# Controller.net
KiCad netlist of a schematic drawn in Altium Designer
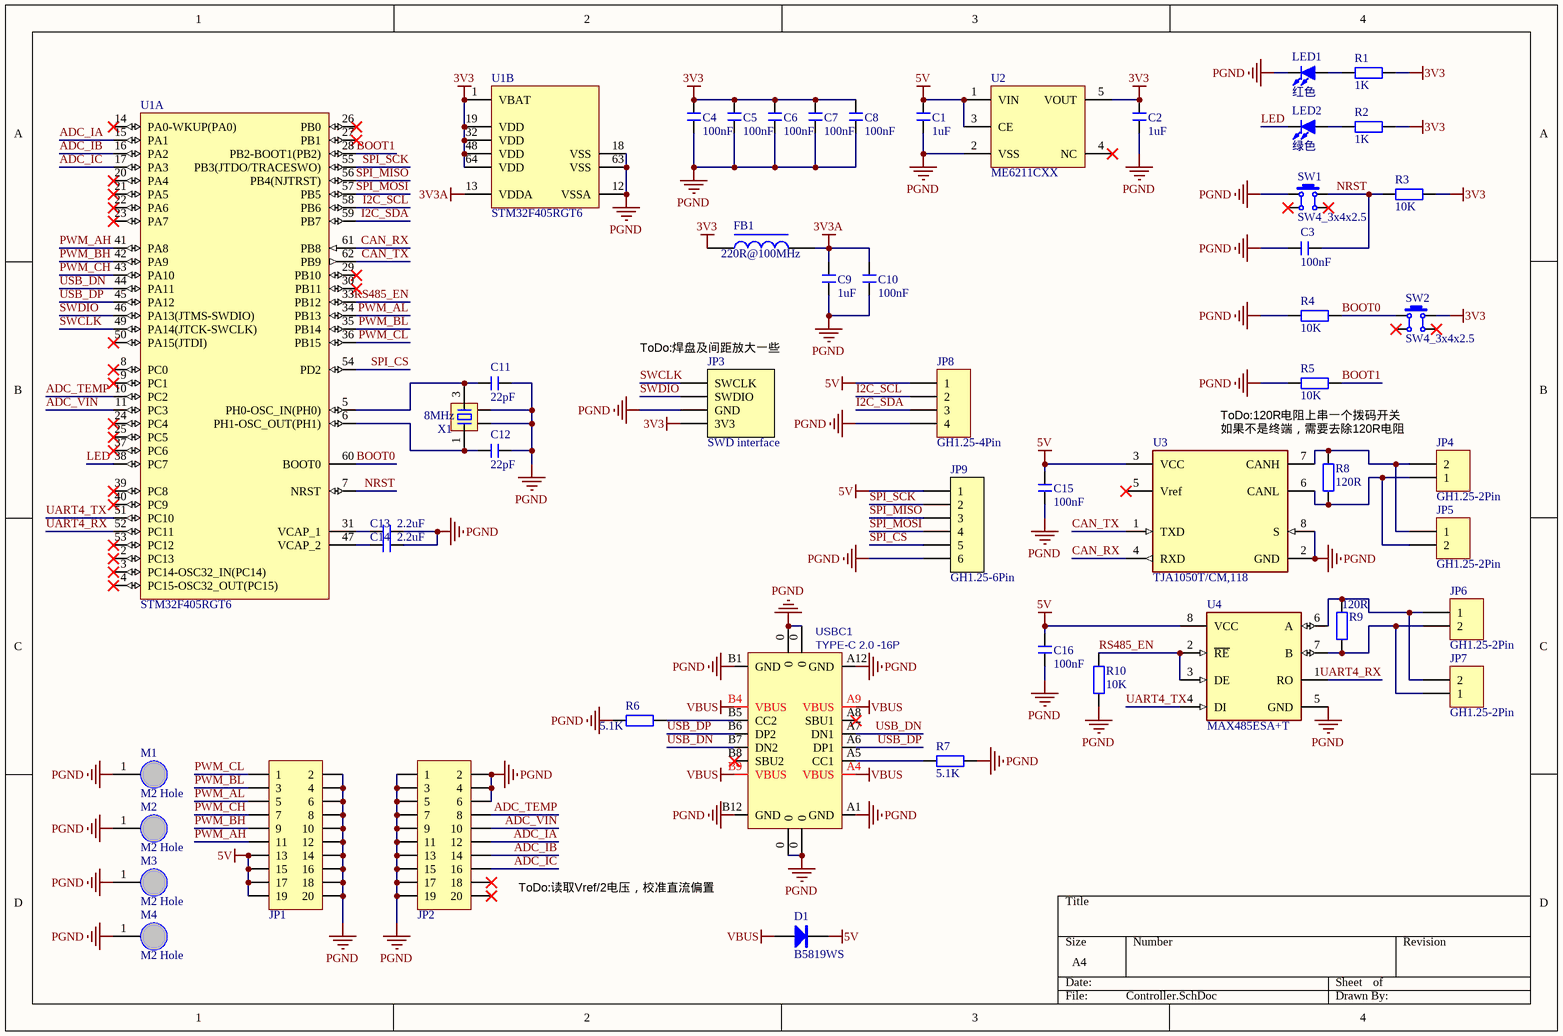
[diagram p0: Controller.SchDoc]

(export (version "E")
  (design (tool "Eeschema 10.0.6"))
  (components
    (comp (ref "C1")
      (value "1uF")
      (footprint "Capacitor_0402_SMD")
      (description "无极性贴片电容")
      (fields (field (name "版权归属") "源创客"))
      (libsource (lib "源创客") (part "C"))
    )
    (comp (ref "C2")
      (value "1uF")
      (footprint "Capacitor_0402_SMD")
      (description "无极性贴片电容")
      (fields (field (name "版权归属") "源创客"))
      (libsource (lib "源创客") (part "C"))
    )
    (comp (ref "C3")
      (value "100nF")
      (footprint "Capacitor_0402_SMD")
      (description "无极性贴片电容")
      (fields (field (name "版权归属") "源创客"))
      (libsource (lib "源创客") (part "C"))
    )
    (comp (ref "C4")
      (value "100nF")
      (footprint "Capacitor_0402_SMD")
      (description "无极性贴片电容")
      (fields (field (name "版权归属") "源创客"))
      (libsource (lib "源创客") (part "C"))
    )
    (comp (ref "C5")
      (value "100nF")
      (footprint "Capacitor_0402_SMD")
      (description "无极性贴片电容")
      (fields (field (name "版权归属") "源创客"))
      (libsource (lib "源创客") (part "C"))
    )
    (comp (ref "C6")
      (value "100nF")
      (footprint "Capacitor_0402_SMD")
      (description "无极性贴片电容")
      (fields (field (name "版权归属") "源创客"))
      (libsource (lib "源创客") (part "C"))
    )
    (comp (ref "C7")
      (value "100nF")
      (footprint "Capacitor_0402_SMD")
      (description "无极性贴片电容")
      (fields (field (name "版权归属") "源创客"))
      (libsource (lib "源创客") (part "C"))
    )
    (comp (ref "C8")
      (value "100nF")
      (footprint "Capacitor_0402_SMD")
      (description "无极性贴片电容")
      (fields (field (name "版权归属") "源创客"))
      (libsource (lib "源创客") (part "C"))
    )
    (comp (ref "C9")
      (value "1uF")
      (footprint "Capacitor_0402_SMD")
      (description "无极性贴片电容")
      (fields (field (name "版权归属") "源创客"))
      (libsource (lib "源创客") (part "C"))
    )
    (comp (ref "C10")
      (value "100nF")
      (footprint "Capacitor_0402_SMD")
      (description "无极性贴片电容")
      (fields (field (name "版权归属") "源创客"))
      (libsource (lib "源创客") (part "C"))
    )
    (comp (ref "C11")
      (value "22pF")
      (footprint "Capacitor_0402_SMD")
      (description "无极性贴片电容")
      (fields (field (name "版权归属") "源创客"))
      (libsource (lib "源创客") (part "C"))
    )
    (comp (ref "C12")
      (value "22pF")
      (footprint "Capacitor_0402_SMD")
      (description "无极性贴片电容")
      (fields (field (name "版权归属") "源创客"))
      (libsource (lib "源创客") (part "C"))
    )
    (comp (ref "C13")
      (value "2.2uF")
      (footprint "Capacitor_0402_SMD")
      (description "无极性贴片电容")
      (fields (field (name "版权归属") "源创客"))
      (libsource (lib "源创客") (part "C"))
    )
    (comp (ref "C14")
      (value "2.2uF")
      (footprint "Capacitor_0402_SMD")
      (description "无极性贴片电容")
      (fields (field (name "版权归属") "源创客"))
      (libsource (lib "源创客") (part "C"))
    )
    (comp (ref "C15")
      (value "100nF")
      (footprint "Capacitor_0402_SMD")
      (description "无极性贴片电容")
      (fields (field (name "版权归属") "源创客"))
      (libsource (lib "源创客") (part "C"))
    )
    (comp (ref "C16")
      (value "100nF")
      (footprint "Capacitor_0402_SMD")
      (description "无极性贴片电容")
      (fields (field (name "版权归属") "源创客"))
      (libsource (lib "源创客") (part "C"))
    )
    (comp (ref "D1")
      (value "B5819WS")
      (footprint "SOD323")
      (description "肖特基二极管")
      (fields (field (name "版权归属") "源创客"))
      (libsource (lib "源创客") (part "1N5819"))
    )
    (comp (ref "FB1")
      (value "220R@100MHz")
      (footprint "FerriteBead_0603_SMD")
      (description "FerriteBead")
      (libsource (lib "源创客") (part "FerriteBead"))
    )
    (comp (ref "JP1")
      (value "Header 2X10")
      (footprint "HDR2.0-LI-2x10P")
      (description "10*2P接插件")
      (libsource (lib "5.5 - 2.54mm(100mil)连接器(XH2.54)") (part "Header 10X2"))
    )
    (comp (ref "JP2")
      (value "Header 2X10")
      (footprint "HDR2.0-LI-2x10P")
      (description "10*2P接插件")
      (libsource (lib "5.5 - 2.54mm(100mil)连接器(XH2.54)") (part "Header 10X2"))
    )
    (comp (ref "JP3")
      (value "SWD interface")
      (footprint "SWD_interface")
      (libsource (lib "Controller") (part "SWD_interface"))
    )
    (comp (ref "JP4")
      (value "GH1.25-2Pin")
      (footprint "A1257WR-S-XP-2Pin")
      (description "CJTconn A1257 Series 1.25mm pitch wire to board connector")
      (libsource (lib "") (part "GH1.25-2Pin_1"))
    )
    (comp (ref "JP5")
      (value "GH1.25-2Pin")
      (footprint "A1257WR-S-XP-2Pin")
      (description "CJTconn A1257 Series 1.25mm pitch wire to board connector")
      (libsource (lib "接插件") (part "GH1.25-2Pin"))
    )
    (comp (ref "JP6")
      (value "GH1.25-2Pin")
      (footprint "A1257WR-S-XP-2Pin")
      (description "CJTconn A1257 Series 1.25mm pitch wire to board connector")
      (libsource (lib "接插件") (part "GH1.25-2Pin"))
    )
    (comp (ref "JP7")
      (value "GH1.25-2Pin")
      (footprint "A1257WR-S-XP-2Pin")
      (description "CJTconn A1257 Series 1.25mm pitch wire to board connector")
      (libsource (lib "") (part "GH1.25-2Pin_1"))
    )
    (comp (ref "JP8")
      (value "GH1.25-4Pin")
      (footprint "A1257WR-S-XP-4Pin")
      (description "CJTconn A1257 Series 1.25mm pitch wire to board connector")
      (libsource (lib "接插件") (part "GH1.25-4Pin"))
    )
    (comp (ref "JP9")
      (value "GH1.25-6Pin")
      (footprint "A1257WR-S-XP-6Pin")
      (description "CJTconn A1257 Series 1.25mm pitch wire to board connector")
      (libsource (lib "接插件") (part "GH1.25-6Pin"))
    )
    (comp (ref "LED1")
      (value "红色")
      (footprint "LED_0603_SMD_RED")
      (description "贴片LED")
      (fields (field (name "版权归属") "源创客"))
      (libsource (lib "源创客") (part "LED-SMD"))
    )
    (comp (ref "LED2")
      (value "绿色")
      (footprint "LED_0603_SMD_GREEN")
      (description "贴片LED")
      (fields (field (name "版权归属") "源创客"))
      (libsource (lib "源创客") (part "LED-SMD"))
    )
    (comp (ref "M1") (value "M2 Hole") (footprint "M2 Hole") (libsource (lib "Controller") (part "M2_hole")))
    (comp (ref "M2") (value "M2 Hole") (footprint "M2 Hole") (libsource (lib "Controller") (part "M2_hole")))
    (comp (ref "M3") (value "M2 Hole") (footprint "M2 Hole") (libsource (lib "Controller") (part "M2_hole")))
    (comp (ref "M4") (value "M2 Hole") (footprint "M2 Hole") (libsource (lib "Controller") (part "M2_hole")))
    (comp (ref "R1")
      (value "1K")
      (footprint "Resistor_0402_SMD")
      (description "贴片电阻")
      (fields (field (name "版权归属") "源创客"))
      (libsource (lib "源创客") (part "R"))
    )
    (comp (ref "R2")
      (value "1K")
      (footprint "Resistor_0402_SMD")
      (description "贴片电阻")
      (fields (field (name "版权归属") "源创客"))
      (libsource (lib "源创客") (part "R"))
    )
    (comp (ref "R3")
      (value "10K")
      (footprint "Resistor_0402_SMD")
      (description "贴片电阻")
      (fields (field (name "版权归属") "源创客"))
      (libsource (lib "源创客") (part "R"))
    )
    (comp (ref "R4")
      (value "10K")
      (footprint "Resistor_0402_SMD")
      (description "贴片电阻")
      (fields (field (name "版权归属") "源创客"))
      (libsource (lib "源创客") (part "R"))
    )
    (comp (ref "R5")
      (value "10K")
      (footprint "Resistor_0402_SMD")
      (description "贴片电阻")
      (fields (field (name "版权归属") "源创客"))
      (libsource (lib "源创客") (part "R"))
    )
    (comp (ref "R6")
      (value "5.1K")
      (footprint "Resistor_0402_SMD")
      (description "贴片电阻")
      (fields (field (name "版权归属") "源创客"))
      (libsource (lib "源创客") (part "R"))
    )
    (comp (ref "R7")
      (value "5.1K")
      (footprint "Resistor_0402_SMD")
      (description "贴片电阻")
      (fields (field (name "版权归属") "源创客"))
      (libsource (lib "源创客") (part "R"))
    )
    (comp (ref "R8")
      (value "120R")
      (footprint "Resistor_0402_SMD")
      (description "贴片电阻")
      (fields (field (name "版权归属") "源创客"))
      (libsource (lib "源创客") (part "R"))
    )
    (comp (ref "R9")
      (value "120R")
      (footprint "Resistor_0402_SMD")
      (description "贴片电阻")
      (fields (field (name "版权归属") "源创客"))
      (libsource (lib "源创客") (part "R"))
    )
    (comp (ref "R10")
      (value "10K")
      (footprint "Resistor_0402_SMD")
      (description "贴片电阻")
      (fields (field (name "版权归属") "源创客"))
      (libsource (lib "源创客") (part "R"))
    )
    (comp (ref "SW1")
      (value "SW4_3x4x2.5")
      (footprint "SW4_3x4x2.5")
      (libsource (lib "Controller") (part "SW4_3x4x2.5"))
    )
    (comp (ref "SW2")
      (value "SW4_3x4x2.5")
      (footprint "SW4_3x4x2.5")
      (libsource (lib "Controller") (part "SW4_3x4x2.5"))
    )
    (comp (ref "U1")
      (value "STM32F405RGT6")
      (footprint "STM-LQFP64_L")
      (fields (field (name "MANUFACTURER") "STMicroelectronics"))
      (libsource (lib "Altium Content Vault") (part "MC-ARM-STM32F4X5-SQ64"))
    )
    (comp (ref "U2")
      (value "ME6211CXX")
      (footprint "ME6211CXX")
      (description "高精度、高纹波抑制比、低噪声、超快响应 LDO")
      (libsource (lib "Controller") (part "ME6211CXX"))
    )
    (comp (ref "U3")
      (value "TJA1050T/CM,118")
      (footprint "FP-SOT96-1-IPC_C")
      (description "IC TRANSCEIVER HALF 1/1 8SO")
      (libsource (lib "Altium Content Vault") (part "cfdefafd38a55dc0607790f57b8a78f"))
    )
    (comp (ref "U4")
      (value "MAX485ESA+T")
      (footprint "FP-S8-2-IPC_C")
      (description "IC TRANSCEIVER HALF 1/1 8SOIC")
      (fields
        (field (name "OCTOPART") "https://octopart.com/max485esa%2Bt-maxim+integrated-40011239")
        (field (name "MANUFACTURER") "Maxim Integrated")
      )
      (libsource (lib "Altium Content Vault") (part "5a32c1deac0ec46b72dd39c04a7e29b"))
    )
    (comp (ref "USBC1")
      (value "TYPE-C 2.0 -16P")
      (footprint "USB-C-SMD_16P")
      (description "USB2.0_Type-C_16Pin母座")
      (libsource (lib "0.6 - 电源-以太网-音频-Type-C USB插座") (part "USB2.0_Type-C_16Pin"))
    )
    (comp (ref "X1")
      (value "8MHz")
      (footprint "OSC 3225-4P")
      (description "4脚无源晶振")
      (fields (field (name "版权归属") "源创客"))
      (libsource (lib "源创客") (part "XTAL-4P"))
    )
  )
  (nets
    (net (code "1") (name "/ADC_IA") (class "Default")
      (node (ref "JP2") (pin "12") (pinfunction "12_12") (pintype "passive"))
      (node (ref "U1") (pin "15") (pinfunction "PA1_15") (pintype "bidirectional"))
    )
    (net (code "2") (name "/ADC_IB") (class "Default")
      (node (ref "JP2") (pin "14") (pinfunction "14_14") (pintype "passive"))
      (node (ref "U1") (pin "16") (pinfunction "PA2_16") (pintype "bidirectional"))
    )
    (net (code "3") (name "/ADC_IC") (class "Default")
      (node (ref "JP2") (pin "16") (pinfunction "16_16") (pintype "passive"))
      (node (ref "U1") (pin "17") (pinfunction "PA3_17") (pintype "bidirectional"))
    )
    (net (code "4") (name "/ADC_TEMP") (class "Default")
      (node (ref "JP2") (pin "8") (pinfunction "8_8") (pintype "passive"))
      (node (ref "U1") (pin "10") (pinfunction "PC2_10") (pintype "bidirectional"))
    )
    (net (code "5") (name "/ADC_VIN") (class "Default")
      (node (ref "JP2") (pin "10") (pinfunction "10_10") (pintype "passive"))
      (node (ref "U1") (pin "11") (pinfunction "PC3_11") (pintype "bidirectional"))
    )
    (net (code "6") (name "/BOOT0") (class "Default")
      (node (ref "R4") (pin "1") (pinfunction "1_1") (pintype "passive"))
      (node (ref "SW2") (pin "2") (pinfunction "2_2") (pintype "passive"))
      (node (ref "U1") (pin "60") (pinfunction "BOOT0_60") (pintype "passive"))
    )
    (net (code "7") (name "/BOOT1") (class "Default")
      (node (ref "R5") (pin "1") (pinfunction "1_1") (pintype "passive"))
      (node (ref "U1") (pin "28") (pinfunction "PB2-BOOT1(PB2)_28") (pintype "bidirectional"))
    )
    (net (code "8") (name "/CAN_RX") (class "Default")
      (node (ref "U1") (pin "61") (pinfunction "PB8_61") (pintype "input"))
      (node (ref "U3") (pin "4") (pinfunction "RXD_4") (pintype "output"))
    )
    (net (code "9") (name "/CAN_TX") (class "Default")
      (node (ref "U1") (pin "62") (pinfunction "PB9_62") (pintype "output"))
      (node (ref "U3") (pin "1") (pinfunction "TXD_1") (pintype "input"))
    )
    (net (code "10") (name "/I2C_SCL") (class "Default")
      (node (ref "JP8") (pin "2") (pinfunction "2_2") (pintype "passive"))
      (node (ref "U1") (pin "58") (pinfunction "PB6_58") (pintype "bidirectional"))
    )
    (net (code "11") (name "/I2C_SDA") (class "Default")
      (node (ref "JP8") (pin "3") (pinfunction "3_3") (pintype "passive"))
      (node (ref "U1") (pin "59") (pinfunction "PB7_59") (pintype "bidirectional"))
    )
    (net (code "12") (name "/LED") (class "Default")
      (node (ref "LED2") (pin "2") (pinfunction "K_2") (pintype "passive"))
      (node (ref "U1") (pin "38") (pinfunction "PC7_38") (pintype "bidirectional"))
    )
    (net (code "13") (name "/NRST") (class "Default")
      (node (ref "C3") (pin "1") (pinfunction "1_1") (pintype "passive"))
      (node (ref "R3") (pin "2") (pinfunction "2_2") (pintype "passive"))
      (node (ref "SW1") (pin "4") (pinfunction "4_4") (pintype "passive"))
      (node (ref "U1") (pin "7") (pinfunction "NRST_7") (pintype "bidirectional"))
    )
    (net (code "14") (name "/PWM_AH") (class "Default")
      (node (ref "JP1") (pin "11") (pinfunction "11_11") (pintype "passive"))
      (node (ref "U1") (pin "41") (pinfunction "PA8_41") (pintype "bidirectional"))
    )
    (net (code "15") (name "/PWM_AL") (class "Default")
      (node (ref "JP1") (pin "5") (pinfunction "5_5") (pintype "passive"))
      (node (ref "U1") (pin "34") (pinfunction "PB13_34") (pintype "bidirectional"))
    )
    (net (code "16") (name "/PWM_BH") (class "Default")
      (node (ref "JP1") (pin "9") (pinfunction "9_9") (pintype "passive"))
      (node (ref "U1") (pin "42") (pinfunction "PA9_42") (pintype "bidirectional"))
    )
    (net (code "17") (name "/PWM_BL") (class "Default")
      (node (ref "JP1") (pin "3") (pinfunction "3_3") (pintype "passive"))
      (node (ref "U1") (pin "35") (pinfunction "PB14_35") (pintype "bidirectional"))
    )
    (net (code "18") (name "/PWM_CH") (class "Default")
      (node (ref "JP1") (pin "7") (pinfunction "7_7") (pintype "passive"))
      (node (ref "U1") (pin "43") (pinfunction "PA10_43") (pintype "bidirectional"))
    )
    (net (code "19") (name "/PWM_CL") (class "Default")
      (node (ref "JP1") (pin "1") (pinfunction "1_1") (pintype "passive"))
      (node (ref "U1") (pin "36") (pinfunction "PB15_36") (pintype "bidirectional"))
    )
    (net (code "20") (name "/RS485_EN") (class "Default")
      (node (ref "R10") (pin "1") (pinfunction "1_1") (pintype "passive"))
      (node (ref "U1") (pin "33") (pinfunction "PB12_33") (pintype "bidirectional"))
      (node (ref "U4") (pin "2") (pinfunction "~{RE}_2") (pintype "input"))
      (node (ref "U4") (pin "3") (pinfunction "DE_3") (pintype "input"))
    )
    (net (code "21") (name "/SPI_CS") (class "Default")
      (node (ref "JP9") (pin "5") (pinfunction "5_5") (pintype "passive"))
      (node (ref "U1") (pin "54") (pinfunction "PD2_54") (pintype "bidirectional"))
    )
    (net (code "22") (name "/SPI_MISO") (class "Default")
      (node (ref "JP9") (pin "3") (pinfunction "3_3") (pintype "passive"))
      (node (ref "U1") (pin "56") (pinfunction "PB4(NJTRST)_56") (pintype "bidirectional"))
    )
    (net (code "23") (name "/SPI_MOSI") (class "Default")
      (node (ref "JP9") (pin "4") (pinfunction "4_4") (pintype "passive"))
      (node (ref "U1") (pin "57") (pinfunction "PB5_57") (pintype "bidirectional"))
    )
    (net (code "24") (name "/SPI_SCK") (class "Default")
      (node (ref "JP9") (pin "2") (pinfunction "2_2") (pintype "passive"))
      (node (ref "U1") (pin "55") (pinfunction "PB3(JTDO/TRACESWO)_55") (pintype "bidirectional"))
    )
    (net (code "25") (name "/SWCLK") (class "Default")
      (node (ref "JP3") (pin "1") (pinfunction "SWCLK_1") (pintype "passive"))
      (node (ref "U1") (pin "49") (pinfunction "PA14(JTCK-SWCLK)_49") (pintype "bidirectional"))
    )
    (net (code "26") (name "/SWDIO") (class "Default")
      (node (ref "JP3") (pin "2") (pinfunction "SWDIO_2") (pintype "passive"))
      (node (ref "U1") (pin "46") (pinfunction "PA13(JTMS-SWDIO)_46") (pintype "bidirectional"))
    )
    (net (code "27") (name "/UART4_RX") (class "Default")
      (node (ref "U1") (pin "52") (pinfunction "PC11_52") (pintype "bidirectional"))
      (node (ref "U4") (pin "1") (pinfunction "RO_1") (pintype "passive"))
    )
    (net (code "28") (name "/UART4_TX") (class "Default")
      (node (ref "U1") (pin "51") (pinfunction "PC10_51") (pintype "bidirectional"))
      (node (ref "U4") (pin "4") (pinfunction "DI_4") (pintype "input"))
    )
    (net (code "29") (name "/USB_DN") (class "Default")
      (node (ref "U1") (pin "44") (pinfunction "PA11_44") (pintype "bidirectional"))
      (node (ref "USBC1") (pin "A7") (pinfunction "DN1_A7") (pintype "passive"))
      (node (ref "USBC1") (pin "B7") (pinfunction "DN2_B7") (pintype "passive"))
    )
    (net (code "30") (name "/USB_DP") (class "Default")
      (node (ref "U1") (pin "45") (pinfunction "PA12_45") (pintype "bidirectional"))
      (node (ref "USBC1") (pin "A6") (pinfunction "DP1_A6") (pintype "passive"))
      (node (ref "USBC1") (pin "B6") (pinfunction "DP2_B6") (pintype "passive"))
    )
    (net (code "31") (name "3V3") (class "Default")
      (node (ref "C2") (pin "2") (pinfunction "2_2") (pintype "passive"))
      (node (ref "C4") (pin "2") (pinfunction "2_2") (pintype "passive"))
      (node (ref "C5") (pin "2") (pinfunction "2_2") (pintype "passive"))
      (node (ref "C6") (pin "2") (pinfunction "2_2") (pintype "passive"))
      (node (ref "C7") (pin "2") (pinfunction "2_2") (pintype "passive"))
      (node (ref "C8") (pin "2") (pinfunction "2_2") (pintype "passive"))
      (node (ref "FB1") (pin "1") (pinfunction "1_1") (pintype "passive"))
      (node (ref "JP3") (pin "4") (pinfunction "3V3_4") (pintype "passive"))
      (node (ref "R1") (pin "2") (pinfunction "2_2") (pintype "passive"))
      (node (ref "R2") (pin "2") (pinfunction "2_2") (pintype "passive"))
      (node (ref "R3") (pin "1") (pinfunction "1_1") (pintype "passive"))
      (node (ref "SW2") (pin "4") (pinfunction "4_4") (pintype "passive"))
      (node (ref "U1") (pin "1") (pinfunction "VBAT_1") (pintype "power_in"))
      (node (ref "U1") (pin "19") (pinfunction "VDD_19") (pintype "power_in"))
      (node (ref "U1") (pin "32") (pinfunction "VDD_32") (pintype "power_in"))
      (node (ref "U1") (pin "48") (pinfunction "VDD_48") (pintype "power_in"))
      (node (ref "U1") (pin "64") (pinfunction "VDD_64") (pintype "power_in"))
      (node (ref "U2") (pin "5") (pinfunction "VOUT_5") (pintype "passive"))
    )
    (net (code "32") (name "3V3A") (class "Default")
      (node (ref "C10") (pin "2") (pinfunction "2_2") (pintype "passive"))
      (node (ref "C9") (pin "2") (pinfunction "2_2") (pintype "passive"))
      (node (ref "FB1") (pin "2") (pinfunction "2_2") (pintype "passive"))
      (node (ref "U1") (pin "13") (pinfunction "VDDA_13") (pintype "power_in"))
    )
    (net (code "33") (name "5V") (class "Default")
      (node (ref "C1") (pin "2") (pinfunction "2_2") (pintype "passive"))
      (node (ref "C15") (pin "1") (pinfunction "1_1") (pintype "passive"))
      (node (ref "C16") (pin "1") (pinfunction "1_1") (pintype "passive"))
      (node (ref "D1") (pin "2") (pinfunction "K_2") (pintype "passive"))
      (node (ref "JP1") (pin "13") (pinfunction "13_13") (pintype "passive"))
      (node (ref "JP1") (pin "15") (pinfunction "15_15") (pintype "passive"))
      (node (ref "JP1") (pin "17") (pinfunction "17_17") (pintype "passive"))
      (node (ref "JP1") (pin "19") (pinfunction "19_19") (pintype "passive"))
      (node (ref "JP8") (pin "1") (pinfunction "1_1") (pintype "passive"))
      (node (ref "JP9") (pin "1") (pinfunction "1_1") (pintype "passive"))
      (node (ref "U2") (pin "1") (pinfunction "VIN_1") (pintype "passive"))
      (node (ref "U2") (pin "3") (pinfunction "CE_3") (pintype "passive"))
      (node (ref "U3") (pin "3") (pinfunction "VCC_3") (pintype "power_in"))
      (node (ref "U4") (pin "8") (pinfunction "VCC_8") (pintype "power_in"))
    )
    (net (code "34") (name "Net-(LED1-A)") (class "Default")
      (node (ref "LED1") (pin "1") (pinfunction "A_1") (pintype "passive"))
      (node (ref "R1") (pin "1") (pinfunction "1_1") (pintype "passive"))
    )
    (net (code "35") (name "Net-(LED2-A)") (class "Default")
      (node (ref "LED2") (pin "1") (pinfunction "A_1") (pintype "passive"))
      (node (ref "R2") (pin "1") (pinfunction "1_1") (pintype "passive"))
    )
    (net (code "36") (name "Net-(U1A-PH0-OSC_IN(PH0))") (class "Default")
      (node (ref "C11") (pin "2") (pinfunction "2_2") (pintype "passive"))
      (node (ref "U1") (pin "5") (pinfunction "PH0-OSC_IN(PH0)_5") (pintype "bidirectional"))
      (node (ref "X1") (pin "3") (pinfunction "3_3") (pintype "passive"))
    )
    (net (code "37") (name "Net-(U1A-PH1-OSC_OUT(PH1))") (class "Default")
      (node (ref "C12") (pin "2") (pinfunction "2_2") (pintype "passive"))
      (node (ref "U1") (pin "6") (pinfunction "PH1-OSC_OUT(PH1)_6") (pintype "bidirectional"))
      (node (ref "X1") (pin "1") (pinfunction "1_1") (pintype "passive"))
    )
    (net (code "38") (name "Net-(U1A-VCAP_1)") (class "Default")
      (node (ref "C13") (pin "2") (pinfunction "2_2") (pintype "passive"))
      (node (ref "U1") (pin "31") (pinfunction "VCAP_1_31") (pintype "power_in"))
    )
    (net (code "39") (name "Net-(U1A-VCAP_2)") (class "Default")
      (node (ref "C14") (pin "2") (pinfunction "2_2") (pintype "passive"))
      (node (ref "U1") (pin "47") (pinfunction "VCAP_2_47") (pintype "power_in"))
    )
    (net (code "40") (name "Net-(U3-CANH)") (class "Default")
      (node (ref "JP4") (pin "2") (pinfunction "2_2") (pintype "passive"))
      (node (ref "JP5") (pin "1") (pinfunction "1_1") (pintype "passive"))
      (node (ref "R8") (pin "1") (pinfunction "1_1") (pintype "passive"))
      (node (ref "U3") (pin "7") (pinfunction "CANH_7") (pintype "passive"))
    )
    (net (code "41") (name "Net-(U3-CANL)") (class "Default")
      (node (ref "JP4") (pin "1") (pinfunction "1_1") (pintype "passive"))
      (node (ref "JP5") (pin "2") (pinfunction "2_2") (pintype "passive"))
      (node (ref "R8") (pin "2") (pinfunction "2_2") (pintype "passive"))
      (node (ref "U3") (pin "6") (pinfunction "CANL_6") (pintype "passive"))
    )
    (net (code "42") (name "Net-(U4-A)") (class "Default")
      (node (ref "JP6") (pin "1") (pinfunction "1_1") (pintype "passive"))
      (node (ref "JP7") (pin "2") (pinfunction "2_2") (pintype "passive"))
      (node (ref "R9") (pin "1") (pinfunction "1_1") (pintype "passive"))
      (node (ref "U4") (pin "6") (pinfunction "A_6") (pintype "bidirectional"))
    )
    (net (code "43") (name "Net-(U4-B)") (class "Default")
      (node (ref "JP6") (pin "2") (pinfunction "2_2") (pintype "passive"))
      (node (ref "JP7") (pin "1") (pinfunction "1_1") (pintype "passive"))
      (node (ref "R9") (pin "2") (pinfunction "2_2") (pintype "passive"))
      (node (ref "U4") (pin "7") (pinfunction "B_7") (pintype "bidirectional"))
    )
    (net (code "44") (name "Net-(USBC1-CC1)") (class "Default")
      (node (ref "R7") (pin "1") (pinfunction "1_1") (pintype "passive"))
      (node (ref "USBC1") (pin "A5") (pinfunction "CC1_A5") (pintype "passive"))
    )
    (net (code "45") (name "Net-(USBC1-CC2)") (class "Default")
      (node (ref "R6") (pin "2") (pinfunction "2_2") (pintype "passive"))
      (node (ref "USBC1") (pin "B5") (pinfunction "CC2_B5") (pintype "passive"))
    )
    (net (code "46") (name "PGND") (class "Default")
      (node (ref "C1") (pin "1") (pinfunction "1_1") (pintype "passive"))
      (node (ref "C10") (pin "1") (pinfunction "1_1") (pintype "passive"))
      (node (ref "C11") (pin "1") (pinfunction "1_1") (pintype "passive"))
      (node (ref "C12") (pin "1") (pinfunction "1_1") (pintype "passive"))
      (node (ref "C13") (pin "1") (pinfunction "1_1") (pintype "passive"))
      (node (ref "C14") (pin "1") (pinfunction "1_1") (pintype "passive"))
      (node (ref "C15") (pin "2") (pinfunction "2_2") (pintype "passive"))
      (node (ref "C16") (pin "2") (pinfunction "2_2") (pintype "passive"))
      (node (ref "C2") (pin "1") (pinfunction "1_1") (pintype "passive"))
      (node (ref "C3") (pin "2") (pinfunction "2_2") (pintype "passive"))
      (node (ref "C4") (pin "1") (pinfunction "1_1") (pintype "passive"))
      (node (ref "C5") (pin "1") (pinfunction "1_1") (pintype "passive"))
      (node (ref "C6") (pin "1") (pinfunction "1_1") (pintype "passive"))
      (node (ref "C7") (pin "1") (pinfunction "1_1") (pintype "passive"))
      (node (ref "C8") (pin "1") (pinfunction "1_1") (pintype "passive"))
      (node (ref "C9") (pin "1") (pinfunction "1_1") (pintype "passive"))
      (node (ref "JP1") (pin "10") (pinfunction "10_10") (pintype "passive"))
      (node (ref "JP1") (pin "12") (pinfunction "12_12") (pintype "passive"))
      (node (ref "JP1") (pin "14") (pinfunction "14_14") (pintype "passive"))
      (node (ref "JP1") (pin "16") (pinfunction "16_16") (pintype "passive"))
      (node (ref "JP1") (pin "18") (pinfunction "18_18") (pintype "passive"))
      (node (ref "JP1") (pin "2") (pinfunction "2_2") (pintype "passive"))
      (node (ref "JP1") (pin "20") (pinfunction "20_20") (pintype "passive"))
      (node (ref "JP1") (pin "4") (pinfunction "4_4") (pintype "passive"))
      (node (ref "JP1") (pin "6") (pinfunction "6_6") (pintype "passive"))
      (node (ref "JP1") (pin "8") (pinfunction "8_8") (pintype "passive"))
      (node (ref "JP2") (pin "1") (pinfunction "1_1") (pintype "passive"))
      (node (ref "JP2") (pin "11") (pinfunction "11_11") (pintype "passive"))
      (node (ref "JP2") (pin "13") (pinfunction "13_13") (pintype "passive"))
      (node (ref "JP2") (pin "15") (pinfunction "15_15") (pintype "passive"))
      (node (ref "JP2") (pin "17") (pinfunction "17_17") (pintype "passive"))
      (node (ref "JP2") (pin "19") (pinfunction "19_19") (pintype "passive"))
      (node (ref "JP2") (pin "2") (pinfunction "2_2") (pintype "passive"))
      (node (ref "JP2") (pin "3") (pinfunction "3_3") (pintype "passive"))
      (node (ref "JP2") (pin "4") (pinfunction "4_4") (pintype "passive"))
      (node (ref "JP2") (pin "5") (pinfunction "5_5") (pintype "passive"))
      (node (ref "JP2") (pin "6") (pinfunction "6_6") (pintype "passive"))
      (node (ref "JP2") (pin "7") (pinfunction "7_7") (pintype "passive"))
      (node (ref "JP2") (pin "9") (pinfunction "9_9") (pintype "passive"))
      (node (ref "JP3") (pin "3") (pinfunction "GND_3") (pintype "passive"))
      (node (ref "JP8") (pin "4") (pinfunction "4_4") (pintype "passive"))
      (node (ref "JP9") (pin "6") (pinfunction "6_6") (pintype "passive"))
      (node (ref "LED1") (pin "2") (pinfunction "K_2") (pintype "passive"))
      (node (ref "M1") (pin "1") (pinfunction "Hole_1") (pintype "passive"))
      (node (ref "M2") (pin "1") (pinfunction "Hole_1") (pintype "passive"))
      (node (ref "M3") (pin "1") (pinfunction "Hole_1") (pintype "passive"))
      (node (ref "M4") (pin "1") (pinfunction "Hole_1") (pintype "passive"))
      (node (ref "R10") (pin "2") (pinfunction "2_2") (pintype "passive"))
      (node (ref "R4") (pin "2") (pinfunction "2_2") (pintype "passive"))
      (node (ref "R5") (pin "2") (pinfunction "2_2") (pintype "passive"))
      (node (ref "R6") (pin "1") (pinfunction "1_1") (pintype "passive"))
      (node (ref "R7") (pin "2") (pinfunction "2_2") (pintype "passive"))
      (node (ref "SW1") (pin "2") (pinfunction "2_2") (pintype "passive"))
      (node (ref "U1") (pin "12") (pinfunction "VSSA_12") (pintype "power_in"))
      (node (ref "U1") (pin "18") (pinfunction "VSS_18") (pintype "power_in"))
      (node (ref "U1") (pin "63") (pinfunction "VSS_63") (pintype "power_in"))
      (node (ref "U2") (pin "2") (pinfunction "VSS_2") (pintype "passive"))
      (node (ref "U3") (pin "2") (pinfunction "GND_2") (pintype "power_in"))
      (node (ref "U3") (pin "8") (pinfunction "S_8") (pintype "input"))
      (node (ref "U4") (pin "5") (pinfunction "GND_5") (pintype "power_in"))
      (node (ref "USBC1") (pin "0") (pinfunction "0_0") (pintype "passive"))
      (node (ref "USBC1") (pin "A1") (pinfunction "GND_A1") (pintype "passive"))
      (node (ref "USBC1") (pin "A12") (pinfunction "GND_A12") (pintype "passive"))
      (node (ref "USBC1") (pin "B1") (pinfunction "GND_B1") (pintype "passive"))
      (node (ref "USBC1") (pin "B12") (pinfunction "GND_B12") (pintype "passive"))
      (node (ref "X1") (pin "2") (pinfunction "2_2") (pintype "passive"))
      (node (ref "X1") (pin "4") (pinfunction "4_4") (pintype "passive"))
    )
    (net (code "47") (name "VBUS") (class "Default")
      (node (ref "D1") (pin "1") (pinfunction "A_1") (pintype "passive"))
      (node (ref "USBC1") (pin "A4") (pinfunction "VBUS_A4") (pintype "passive"))
      (node (ref "USBC1") (pin "A9") (pinfunction "VBUS_A9") (pintype "passive"))
      (node (ref "USBC1") (pin "B4") (pinfunction "VBUS_B4") (pintype "passive"))
      (node (ref "USBC1") (pin "B9") (pinfunction "VBUS_B9") (pintype "passive"))
    )
    (net (code "48") (name "unconnected-(JP2-Pad18)") (class "Default")
      (node (ref "JP2") (pin "18") (pinfunction "18_18") (pintype "passive+no_connect"))
    )
    (net (code "49") (name "unconnected-(JP2-Pad20)") (class "Default")
      (node (ref "JP2") (pin "20") (pinfunction "20_20") (pintype "passive+no_connect"))
    )
    (net (code "50") (name "unconnected-(SW1-Pad1)") (class "Default")
      (node (ref "SW1") (pin "1") (pinfunction "1_1") (pintype "passive+no_connect"))
    )
    (net (code "51") (name "unconnected-(SW1-Pad3)") (class "Default")
      (node (ref "SW1") (pin "3") (pinfunction "3_3") (pintype "passive+no_connect"))
    )
    (net (code "52") (name "unconnected-(SW2-Pad1)") (class "Default")
      (node (ref "SW2") (pin "1") (pinfunction "1_1") (pintype "passive+no_connect"))
    )
    (net (code "53") (name "unconnected-(SW2-Pad3)") (class "Default")
      (node (ref "SW2") (pin "3") (pinfunction "3_3") (pintype "passive+no_connect"))
    )
    (net (code "54") (name "unconnected-(U1A-PA0-WKUP(PA0)-Pad14)") (class "Default")
      (node (ref "U1") (pin "14") (pinfunction "PA0-WKUP(PA0)_14") (pintype "bidirectional+no_connect"))
    )
    (net (code "55") (name "unconnected-(U1A-PA4-Pad20)") (class "Default")
      (node (ref "U1") (pin "20") (pinfunction "PA4_20") (pintype "bidirectional+no_connect"))
    )
    (net (code "56") (name "unconnected-(U1A-PA5-Pad21)") (class "Default")
      (node (ref "U1") (pin "21") (pinfunction "PA5_21") (pintype "bidirectional+no_connect"))
    )
    (net (code "57") (name "unconnected-(U1A-PA6-Pad22)") (class "Default")
      (node (ref "U1") (pin "22") (pinfunction "PA6_22") (pintype "bidirectional+no_connect"))
    )
    (net (code "58") (name "unconnected-(U1A-PA7-Pad23)") (class "Default")
      (node (ref "U1") (pin "23") (pinfunction "PA7_23") (pintype "bidirectional+no_connect"))
    )
    (net (code "59") (name "unconnected-(U1A-PA15(JTDI)-Pad50)") (class "Default")
      (node (ref "U1") (pin "50") (pinfunction "PA15(JTDI)_50") (pintype "bidirectional+no_connect"))
    )
    (net (code "60") (name "unconnected-(U1A-PB0-Pad26)") (class "Default")
      (node (ref "U1") (pin "26") (pinfunction "PB0_26") (pintype "bidirectional+no_connect"))
    )
    (net (code "61") (name "unconnected-(U1A-PB1-Pad27)") (class "Default")
      (node (ref "U1") (pin "27") (pinfunction "PB1_27") (pintype "bidirectional+no_connect"))
    )
    (net (code "62") (name "unconnected-(U1A-PB10-Pad29)") (class "Default")
      (node (ref "U1") (pin "29") (pinfunction "PB10_29") (pintype "bidirectional+no_connect"))
    )
    (net (code "63") (name "unconnected-(U1A-PB11-Pad30)") (class "Default")
      (node (ref "U1") (pin "30") (pinfunction "PB11_30") (pintype "bidirectional+no_connect"))
    )
    (net (code "64") (name "unconnected-(U1A-PC0-Pad8)") (class "Default")
      (node (ref "U1") (pin "8") (pinfunction "PC0_8") (pintype "bidirectional+no_connect"))
    )
    (net (code "65") (name "unconnected-(U1A-PC1-Pad9)") (class "Default")
      (node (ref "U1") (pin "9") (pinfunction "PC1_9") (pintype "bidirectional+no_connect"))
    )
    (net (code "66") (name "unconnected-(U1A-PC4-Pad24)") (class "Default")
      (node (ref "U1") (pin "24") (pinfunction "PC4_24") (pintype "bidirectional+no_connect"))
    )
    (net (code "67") (name "unconnected-(U1A-PC5-Pad25)") (class "Default")
      (node (ref "U1") (pin "25") (pinfunction "PC5_25") (pintype "bidirectional+no_connect"))
    )
    (net (code "68") (name "unconnected-(U1A-PC6-Pad37)") (class "Default")
      (node (ref "U1") (pin "37") (pinfunction "PC6_37") (pintype "bidirectional+no_connect"))
    )
    (net (code "69") (name "unconnected-(U1A-PC8-Pad39)") (class "Default")
      (node (ref "U1") (pin "39") (pinfunction "PC8_39") (pintype "bidirectional+no_connect"))
    )
    (net (code "70") (name "unconnected-(U1A-PC9-Pad40)") (class "Default")
      (node (ref "U1") (pin "40") (pinfunction "PC9_40") (pintype "bidirectional+no_connect"))
    )
    (net (code "71") (name "unconnected-(U1A-PC12-Pad53)") (class "Default")
      (node (ref "U1") (pin "53") (pinfunction "PC12_53") (pintype "bidirectional+no_connect"))
    )
    (net (code "72") (name "unconnected-(U1A-PC13-Pad2)") (class "Default")
      (node (ref "U1") (pin "2") (pinfunction "PC13_2") (pintype "bidirectional+no_connect"))
    )
    (net (code "73") (name "unconnected-(U1A-PC14-OSC32_IN(PC14)-Pad3)") (class "Default")
      (node (ref "U1") (pin "3") (pinfunction "PC14-OSC32_IN(PC14)_3") (pintype "bidirectional+no_connect"))
    )
    (net (code "74") (name "unconnected-(U1A-PC15-OSC32_OUT(PC15)-Pad4)") (class "Default")
      (node (ref "U1") (pin "4") (pinfunction "PC15-OSC32_OUT(PC15)_4") (pintype "bidirectional+no_connect"))
    )
    (net (code "75") (name "unconnected-(U2-NC-Pad4)") (class "Default")
      (node (ref "U2") (pin "4") (pinfunction "NC_4") (pintype "passive+no_connect"))
    )
    (net (code "76") (name "unconnected-(U3-Vref-Pad5)") (class "Default")
      (node (ref "U3") (pin "5") (pinfunction "Vref_5") (pintype "power_in+no_connect"))
    )
    (net (code "77") (name "unconnected-(USBC1-SBU1-PadA8)") (class "Default")
      (node (ref "USBC1") (pin "A8") (pinfunction "SBU1_A8") (pintype "passive+no_connect"))
    )
    (net (code "78") (name "unconnected-(USBC1-SBU2-PadB8)") (class "Default")
      (node (ref "USBC1") (pin "B8") (pinfunction "SBU2_B8") (pintype "passive+no_connect"))
    )
  )
)
